# uC.net
KiCad netlist of a schematic drawn in Altium Designer
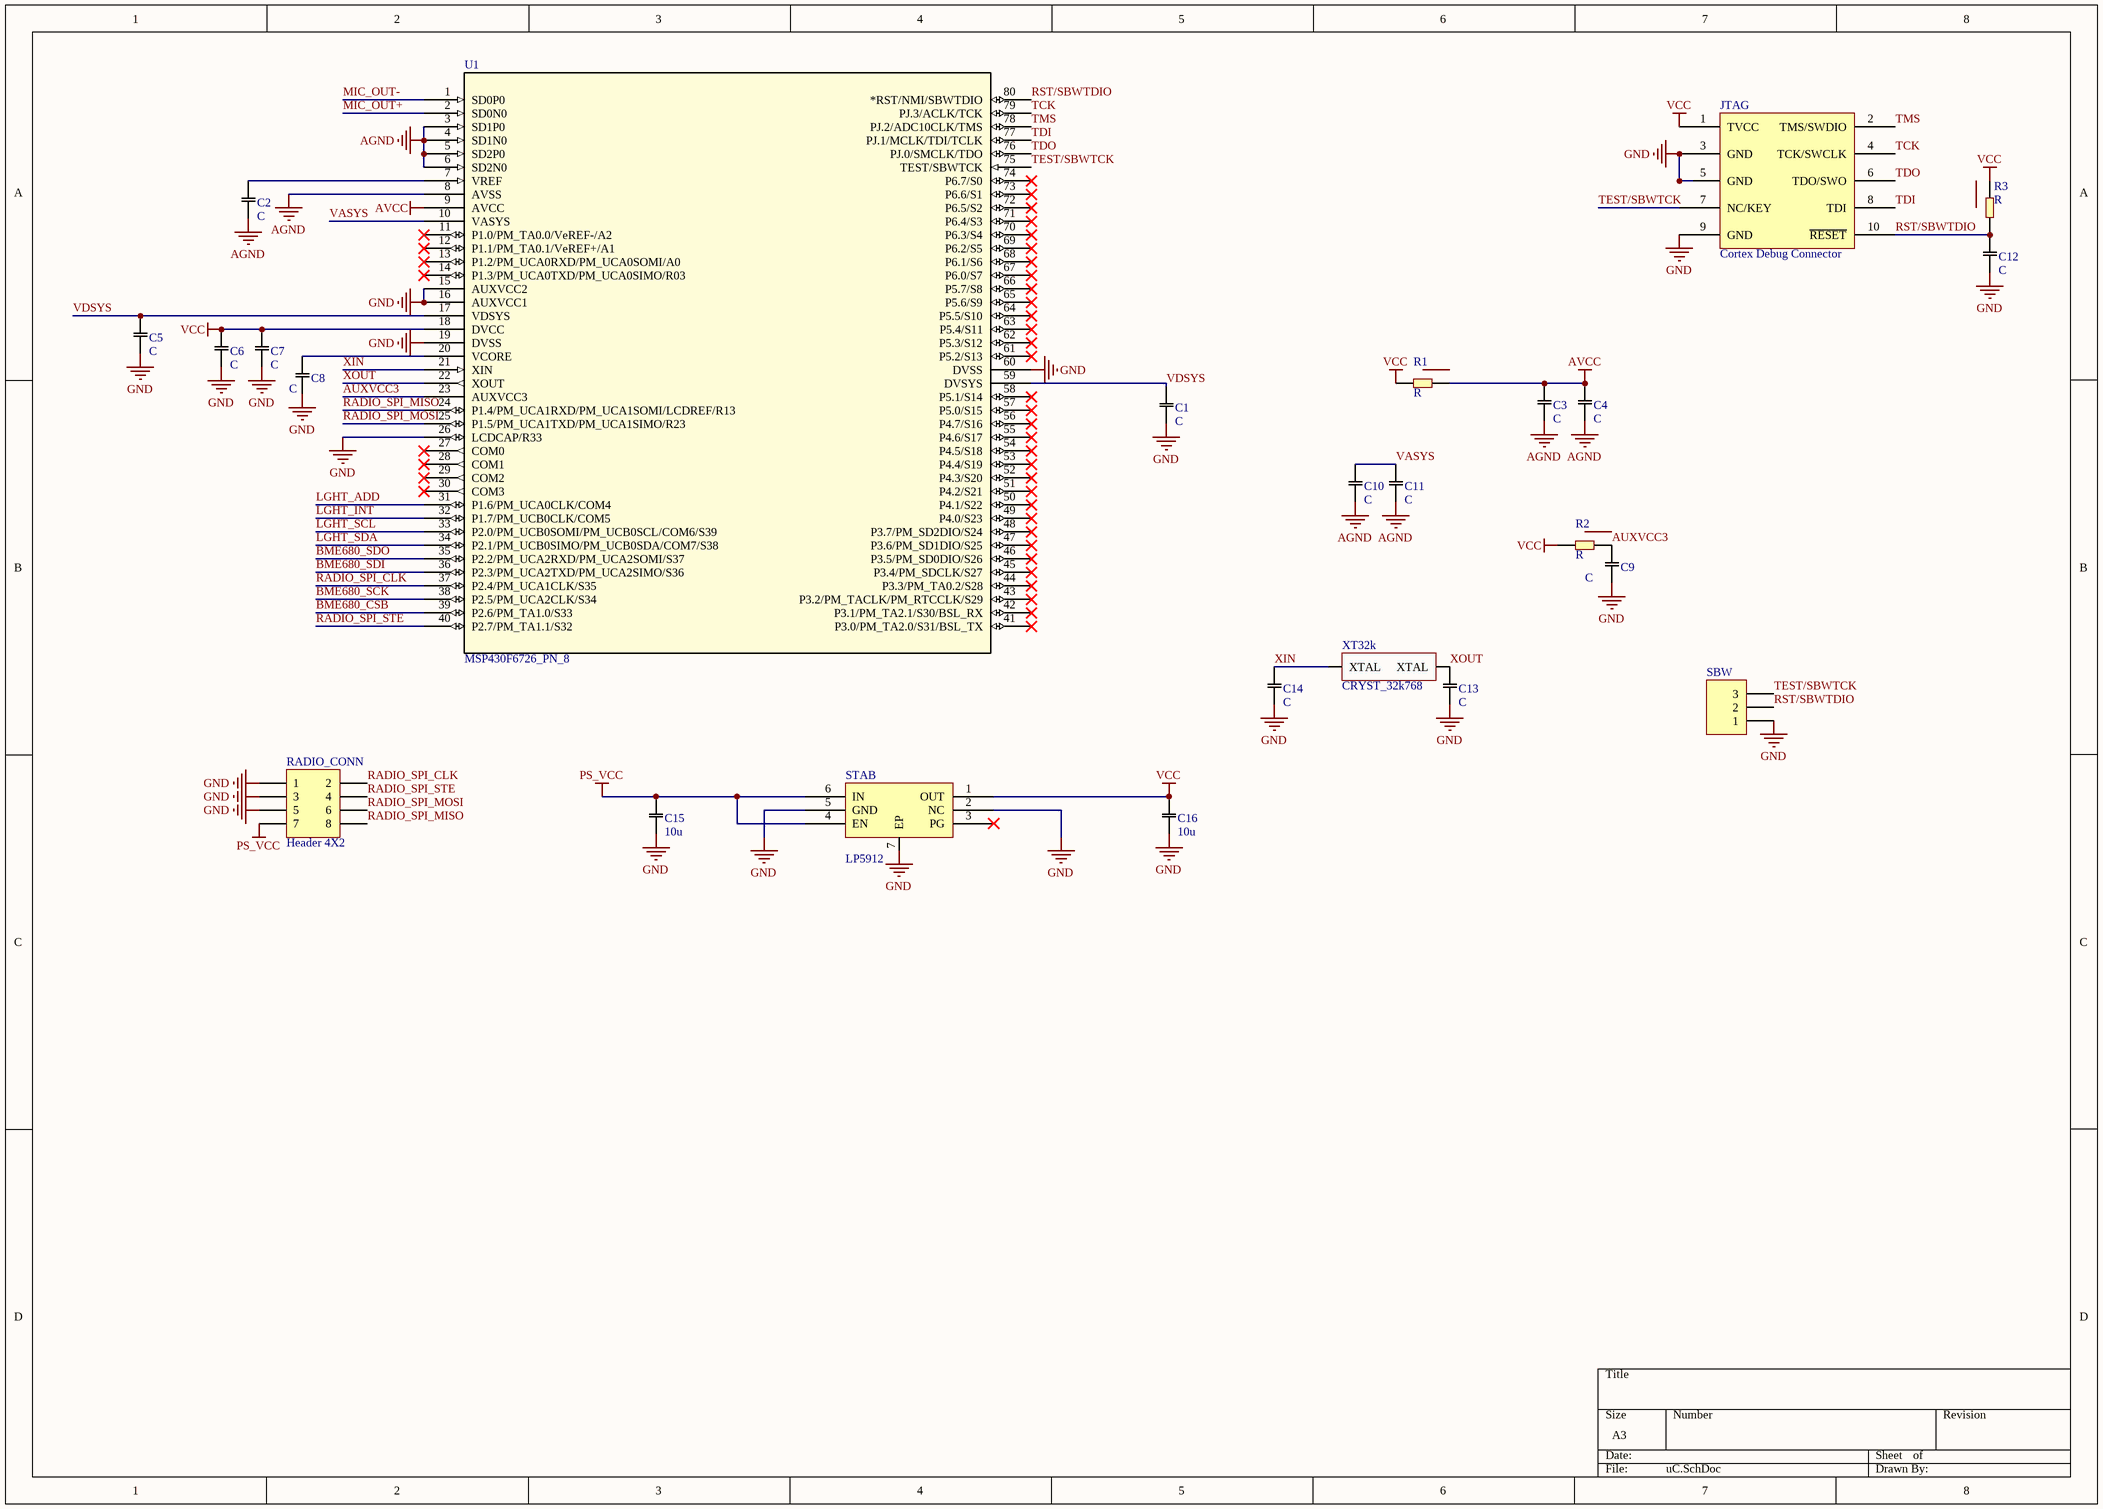
[diagram p0: uC.SchDoc]

(export (version "E")
  (design (tool "Eeschema 10.0.6"))
  (components
    (comp (ref "C1")
      (value "C")
      (footprint "402")
      (description "Capacitor")
      (libsource (lib "pass_comp") (part "C"))
    )
    (comp (ref "C2")
      (value "C")
      (footprint "402")
      (description "Capacitor")
      (libsource (lib "pass_comp") (part "C"))
    )
    (comp (ref "C3")
      (value "C")
      (footprint "402")
      (description "Capacitor")
      (libsource (lib "pass_comp") (part "C"))
    )
    (comp (ref "C4")
      (value "C")
      (footprint "402")
      (description "Capacitor")
      (libsource (lib "pass_comp") (part "C"))
    )
    (comp (ref "C5")
      (value "C")
      (footprint "402")
      (description "Capacitor")
      (libsource (lib "pass_comp") (part "C"))
    )
    (comp (ref "C6")
      (value "C")
      (footprint "402")
      (description "Capacitor")
      (libsource (lib "pass_comp") (part "C"))
    )
    (comp (ref "C7")
      (value "C")
      (footprint "402")
      (description "Capacitor")
      (libsource (lib "pass_comp") (part "C"))
    )
    (comp (ref "C8")
      (value "C")
      (footprint "402")
      (description "Capacitor")
      (libsource (lib "pass_comp") (part "C"))
    )
    (comp (ref "C9")
      (value "C")
      (footprint "402")
      (description "Capacitor")
      (libsource (lib "pass_comp") (part "C"))
    )
    (comp (ref "C10")
      (value "C")
      (footprint "402")
      (description "Capacitor")
      (libsource (lib "pass_comp") (part "C"))
    )
    (comp (ref "C11")
      (value "C")
      (footprint "402")
      (description "Capacitor")
      (libsource (lib "pass_comp") (part "C"))
    )
    (comp (ref "C12")
      (value "C")
      (footprint "402")
      (description "Capacitor")
      (libsource (lib "pass_comp") (part "C"))
    )
    (comp (ref "C13")
      (value "C")
      (footprint "402")
      (description "Capacitor")
      (libsource (lib "pass_comp") (part "C"))
    )
    (comp (ref "C14")
      (value "C")
      (footprint "402")
      (description "Capacitor")
      (libsource (lib "pass_comp") (part "C"))
    )
    (comp (ref "C15")
      (value "10u")
      (footprint "402")
      (description "Capacitor")
      (libsource (lib "pass_comp") (part "C"))
    )
    (comp (ref "C16")
      (value "10u")
      (footprint "402")
      (description "Capacitor")
      (libsource (lib "pass_comp") (part "C"))
    )
    (comp (ref "JTAG")
      (value "Cortex Debug Connector")
      (footprint "JTAG_HEADER")
      (libsource (lib "env_sens") (part "Cortex Debug Connector"))
    )
    (comp (ref "R1") (value "R") (footprint "402") (description "Resistor") (libsource (lib "") (part "R_1")))
    (comp (ref "R2") (value "R") (footprint "402") (description "Resistor") (libsource (lib "") (part "R_1")))
    (comp (ref "R3")
      (value "R")
      (footprint "402")
      (description "Resistor")
      (libsource (lib "pass_comp") (part "R"))
    )
    (comp (ref "RADIO_CONN")
      (value "Header 4X2")
      (footprint "HDR2X4")
      (description "Header, 4-Pin, Dual row")
      (fields (field (name "PUBLISHER") "Altium Limited"))
      (libsource (lib "Miscellaneous Connectors") (part "Header 4X2"))
    )
    (comp (ref "SBW")
      (value "~")
      (footprint "HDR1X3")
      (description "Header, 3-Pin")
      (fields (field (name "PUBLISHER") "Altium Limited"))
      (libsource (lib "Miscellaneous Connectors") (part "Header 3"))
    )
    (comp (ref "STAB") (value "LP5912") (footprint "WSON-6") (libsource (lib "env_sens") (part "LP5912")))
    (comp (ref "U1")
      (value "MSP430F6726_PN_8")
      (footprint "PN80-L")
      (description "Imported")
      (fields
        (field (name "MANUFACTURER_PART_NUMBER") "msp430f6726_pn_80")
        (field (name "GENERIC_PART_NUMBER") "MSP430F6726")
      )
      (libsource (lib "env_sens") (part "MSP430F6726_PN_8"))
    )
    (comp (ref "XT32k")
      (value "CRYST_32k768")
      (footprint "CRYST 32.768 kHz")
      (libsource (lib "env_sens") (part "CRYST_32k768"))
    )
  )
  (nets
    (net (code "1") (name "/AUXVCC3") (class "Default")
      (node (ref "C9") (pin "2") (pintype "passive"))
      (node (ref "R2") (pin "2") (pintype "passive"))
      (node (ref "U1") (pin "23") (pinfunction "AUXVCC3_23") (pintype "power_in"))
    )
    (net (code "2") (name "/BME680_CSB") (class "Default")
      (node (ref "U1") (pin "39") (pinfunction "P2.6/PM_TA1.0/S33_39") (pintype "bidirectional"))
    )
    (net (code "3") (name "/BME680_SCK") (class "Default")
      (node (ref "U1") (pin "38") (pinfunction "P2.5/PM_UCA2CLK/S34_38") (pintype "bidirectional"))
    )
    (net (code "4") (name "/BME680_SDI") (class "Default")
      (node (ref "U1") (pin "36") (pinfunction "P2.3/PM_UCA2TXD/PM_UCA2SIMO/S36_36") (pintype "bidirectional"))
    )
    (net (code "5") (name "/BME680_SDO") (class "Default")
      (node (ref "U1") (pin "35") (pinfunction "P2.2/PM_UCA2RXD/PM_UCA2SOMI/S37_35") (pintype "bidirectional"))
    )
    (net (code "6") (name "/LGHT_ADD") (class "Default")
      (node (ref "U1") (pin "31") (pinfunction "P1.6/PM_UCA0CLK/COM4_31") (pintype "bidirectional"))
    )
    (net (code "7") (name "/LGHT_INT") (class "Default")
      (node (ref "U1") (pin "32") (pinfunction "P1.7/PM_UCB0CLK/COM5_32") (pintype "bidirectional"))
    )
    (net (code "8") (name "/LGHT_SCL") (class "Default")
      (node (ref "U1") (pin "33") (pinfunction "P2.0/PM_UCB0SOMI/PM_UCB0SCL/COM6/S39_33") (pintype "bidirectional"))
    )
    (net (code "9") (name "/LGHT_SDA") (class "Default")
      (node (ref "U1") (pin "34") (pinfunction "P2.1/PM_UCB0SIMO/PM_UCB0SDA/COM7/S38_34") (pintype "bidirectional"))
    )
    (net (code "10") (name "/MIC_OUT+") (class "Default")
      (node (ref "U1") (pin "2") (pinfunction "SD0N0_2") (pintype "input"))
    )
    (net (code "11") (name "/MIC_OUT-") (class "Default")
      (node (ref "U1") (pin "1") (pinfunction "SD0P0_1") (pintype "input"))
    )
    (net (code "12") (name "/RADIO_SPI_CLK") (class "Default")
      (node (ref "RADIO_CONN") (pin "2") (pinfunction "2_2") (pintype "passive"))
      (node (ref "U1") (pin "37") (pinfunction "P2.4/PM_UCA1CLK/S35_37") (pintype "bidirectional"))
    )
    (net (code "13") (name "/RADIO_SPI_MISO") (class "Default")
      (node (ref "RADIO_CONN") (pin "8") (pinfunction "8_8") (pintype "passive"))
      (node (ref "U1") (pin "24") (pinfunction "P1.4/PM_UCA1RXD/PM_UCA1SOMI/LCDREF/R13_24") (pintype "bidirectional"))
    )
    (net (code "14") (name "/RADIO_SPI_MOSI") (class "Default")
      (node (ref "RADIO_CONN") (pin "6") (pinfunction "6_6") (pintype "passive"))
      (node (ref "U1") (pin "25") (pinfunction "P1.5/PM_UCA1TXD/PM_UCA1SIMO/R23_25") (pintype "bidirectional"))
    )
    (net (code "15") (name "/RADIO_SPI_STE") (class "Default")
      (node (ref "RADIO_CONN") (pin "4") (pinfunction "4_4") (pintype "passive"))
      (node (ref "U1") (pin "40") (pinfunction "P2.7/PM_TA1.1/S32_40") (pintype "bidirectional"))
    )
    (net (code "16") (name "/RST{slash}SBWTDIO") (class "Default")
      (node (ref "C12") (pin "2") (pintype "passive"))
      (node (ref "JTAG") (pin "10") (pinfunction "~{RESET}_10") (pintype "passive"))
      (node (ref "R3") (pin "1") (pintype "passive"))
      (node (ref "SBW") (pin "2") (pinfunction "2_2") (pintype "passive"))
      (node (ref "U1") (pin "80") (pinfunction "*RST/NMI/SBWTDIO_80") (pintype "bidirectional"))
    )
    (net (code "17") (name "/TCK") (class "Default")
      (node (ref "JTAG") (pin "4") (pinfunction "TCK/SWCLK_4") (pintype "passive"))
      (node (ref "U1") (pin "79") (pinfunction "PJ.3/ACLK/TCK_79") (pintype "bidirectional"))
    )
    (net (code "18") (name "/TDI") (class "Default")
      (node (ref "JTAG") (pin "8") (pinfunction "TDI_8") (pintype "passive"))
      (node (ref "U1") (pin "77") (pinfunction "PJ.1/MCLK/TDI/TCLK_77") (pintype "bidirectional"))
    )
    (net (code "19") (name "/TDO") (class "Default")
      (node (ref "JTAG") (pin "6") (pinfunction "TDO/SWO_6") (pintype "passive"))
      (node (ref "U1") (pin "76") (pinfunction "PJ.0/SMCLK/TDO_76") (pintype "bidirectional"))
    )
    (net (code "20") (name "/TEST{slash}SBWTCK") (class "Default")
      (node (ref "JTAG") (pin "7") (pinfunction "NC/KEY_7") (pintype "passive"))
      (node (ref "SBW") (pin "3") (pinfunction "3_3") (pintype "passive"))
      (node (ref "U1") (pin "75") (pinfunction "TEST/SBWTCK_75") (pintype "input"))
    )
    (net (code "21") (name "/TMS") (class "Default")
      (node (ref "JTAG") (pin "2") (pinfunction "TMS/SWDIO_2") (pintype "passive"))
      (node (ref "U1") (pin "78") (pinfunction "PJ.2/ADC10CLK/TMS_78") (pintype "bidirectional"))
    )
    (net (code "22") (name "/VASYS") (class "Default")
      (node (ref "C10") (pin "2") (pintype "passive"))
      (node (ref "C11") (pin "2") (pintype "passive"))
      (node (ref "U1") (pin "10") (pinfunction "VASYS_10") (pintype "power_in"))
    )
    (net (code "23") (name "/VDSYS") (class "Default")
      (node (ref "C1") (pin "2") (pintype "passive"))
      (node (ref "C5") (pin "2") (pintype "passive"))
      (node (ref "U1") (pin "17") (pinfunction "VDSYS_17") (pintype "power_in"))
      (node (ref "U1") (pin "59") (pinfunction "DVSYS_59") (pintype "power_in"))
    )
    (net (code "24") (name "/XIN") (class "Default")
      (node (ref "C14") (pin "2") (pintype "passive"))
      (node (ref "U1") (pin "21") (pinfunction "XIN_21") (pintype "input"))
      (node (ref "XT32k") (pin "2") (pinfunction "XTAL_2") (pintype "passive"))
    )
    (net (code "25") (name "/XOUT") (class "Default")
      (node (ref "C13") (pin "2") (pintype "passive"))
      (node (ref "U1") (pin "22") (pinfunction "XOUT_22") (pintype "output"))
      (node (ref "XT32k") (pin "1") (pinfunction "XTAL_1") (pintype "passive"))
    )
    (net (code "26") (name "AGND") (class "Default")
      (node (ref "C10") (pin "1") (pintype "passive"))
      (node (ref "C11") (pin "1") (pintype "passive"))
      (node (ref "C2") (pin "1") (pintype "passive"))
      (node (ref "C3") (pin "1") (pintype "passive"))
      (node (ref "C4") (pin "1") (pintype "passive"))
      (node (ref "U1") (pin "3") (pinfunction "SD1P0_3") (pintype "input"))
      (node (ref "U1") (pin "4") (pinfunction "SD1N0_4") (pintype "input"))
      (node (ref "U1") (pin "5") (pinfunction "SD2P0_5") (pintype "input"))
      (node (ref "U1") (pin "6") (pinfunction "SD2N0_6") (pintype "input"))
      (node (ref "U1") (pin "8") (pinfunction "AVSS_8") (pintype "power_in"))
    )
    (net (code "27") (name "AVCC") (class "Default")
      (node (ref "C3") (pin "2") (pintype "passive"))
      (node (ref "C4") (pin "2") (pintype "passive"))
      (node (ref "R1") (pin "2") (pintype "passive"))
      (node (ref "U1") (pin "9") (pinfunction "AVCC_9") (pintype "power_in"))
    )
    (net (code "28") (name "GND") (class "Default")
      (node (ref "C1") (pin "1") (pintype "passive"))
      (node (ref "C12") (pin "1") (pintype "passive"))
      (node (ref "C13") (pin "1") (pintype "passive"))
      (node (ref "C14") (pin "1") (pintype "passive"))
      (node (ref "C15") (pin "1") (pintype "passive"))
      (node (ref "C16") (pin "1") (pintype "passive"))
      (node (ref "C5") (pin "1") (pintype "passive"))
      (node (ref "C6") (pin "1") (pintype "passive"))
      (node (ref "C7") (pin "1") (pintype "passive"))
      (node (ref "C8") (pin "1") (pintype "passive"))
      (node (ref "C9") (pin "1") (pintype "passive"))
      (node (ref "JTAG") (pin "3") (pinfunction "GND_3") (pintype "passive"))
      (node (ref "JTAG") (pin "5") (pinfunction "GND_5") (pintype "passive"))
      (node (ref "JTAG") (pin "9") (pinfunction "GND_9") (pintype "passive"))
      (node (ref "RADIO_CONN") (pin "1") (pinfunction "1_1") (pintype "passive"))
      (node (ref "RADIO_CONN") (pin "3") (pinfunction "3_3") (pintype "passive"))
      (node (ref "RADIO_CONN") (pin "5") (pinfunction "5_5") (pintype "passive"))
      (node (ref "SBW") (pin "1") (pinfunction "1_1") (pintype "passive"))
      (node (ref "STAB") (pin "2") (pinfunction "NC_2") (pintype "passive"))
      (node (ref "STAB") (pin "5") (pinfunction "GND_5") (pintype "passive"))
      (node (ref "STAB") (pin "7") (pinfunction "EP_7") (pintype "passive"))
      (node (ref "U1") (pin "15") (pinfunction "AUXVCC2_15") (pintype "power_in"))
      (node (ref "U1") (pin "16") (pinfunction "AUXVCC1_16") (pintype "power_in"))
      (node (ref "U1") (pin "19") (pinfunction "DVSS_19") (pintype "power_in"))
      (node (ref "U1") (pin "26") (pinfunction "LCDCAP/R33_26") (pintype "bidirectional"))
      (node (ref "U1") (pin "60") (pinfunction "DVSS_60") (pintype "power_in"))
    )
    (net (code "29") (name "Net-(U1-VCORE)") (class "Default")
      (node (ref "C8") (pin "2") (pintype "passive"))
      (node (ref "U1") (pin "20") (pinfunction "VCORE_20") (pintype "power_in"))
    )
    (net (code "30") (name "Net-(U1-VREF)") (class "Default")
      (node (ref "C2") (pin "2") (pintype "passive"))
      (node (ref "U1") (pin "7") (pinfunction "VREF_7") (pintype "input"))
    )
    (net (code "31") (name "PS_VCC") (class "Default")
      (node (ref "C15") (pin "2") (pintype "passive"))
      (node (ref "RADIO_CONN") (pin "7") (pinfunction "7_7") (pintype "passive"))
      (node (ref "STAB") (pin "4") (pinfunction "EN_4") (pintype "passive"))
      (node (ref "STAB") (pin "6") (pinfunction "IN_6") (pintype "passive"))
    )
    (net (code "32") (name "VCC") (class "Default")
      (node (ref "C16") (pin "2") (pintype "passive"))
      (node (ref "C6") (pin "2") (pintype "passive"))
      (node (ref "C7") (pin "2") (pintype "passive"))
      (node (ref "JTAG") (pin "1") (pinfunction "TVCC_1") (pintype "passive"))
      (node (ref "R1") (pin "1") (pintype "passive"))
      (node (ref "R2") (pin "1") (pintype "passive"))
      (node (ref "R3") (pin "2") (pintype "passive"))
      (node (ref "STAB") (pin "1") (pinfunction "OUT_1") (pintype "passive"))
      (node (ref "U1") (pin "18") (pinfunction "DVCC_18") (pintype "power_in"))
    )
    (net (code "33") (name "unconnected-(STAB-PG-Pad3)") (class "Default")
      (node (ref "STAB") (pin "3") (pinfunction "PG_3") (pintype "passive+no_connect"))
    )
    (net (code "34") (name "unconnected-(U1-COM0-Pad27)") (class "Default")
      (node (ref "U1") (pin "27") (pinfunction "COM0_27") (pintype "output+no_connect"))
    )
    (net (code "35") (name "unconnected-(U1-COM1-Pad28)") (class "Default")
      (node (ref "U1") (pin "28") (pinfunction "COM1_28") (pintype "output+no_connect"))
    )
    (net (code "36") (name "unconnected-(U1-COM2-Pad29)") (class "Default")
      (node (ref "U1") (pin "29") (pinfunction "COM2_29") (pintype "output+no_connect"))
    )
    (net (code "37") (name "unconnected-(U1-COM3-Pad30)") (class "Default")
      (node (ref "U1") (pin "30") (pinfunction "COM3_30") (pintype "output+no_connect"))
    )
    (net (code "38") (name "unconnected-(U1-P1.0{slash}PM_TA0.0{slash}VeREF-{slash}A2-Pad11)") (class "Default")
      (node (ref "U1") (pin "11") (pinfunction "P1.0/PM_TA0.0/VeREF-/A2_11") (pintype "bidirectional+no_connect"))
    )
    (net (code "39") (name "unconnected-(U1-P1.1{slash}PM_TA0.1{slash}VeREF+{slash}A1-Pad12)") (class "Default")
      (node (ref "U1") (pin "12") (pinfunction "P1.1/PM_TA0.1/VeREF+/A1_12") (pintype "bidirectional+no_connect"))
    )
    (net (code "40") (name "unconnected-(U1-P1.2{slash}PM_UCA0RXD{slash}PM_UCA0SOMI{slash}A0-Pad13)") (class "Default")
      (node (ref "U1") (pin "13") (pinfunction "P1.2/PM_UCA0RXD/PM_UCA0SOMI/A0_13") (pintype "bidirectional+no_connect"))
    )
    (net (code "41") (name "unconnected-(U1-P1.3{slash}PM_UCA0TXD{slash}PM_UCA0SIMO{slash}R03-Pad14)") (class "Default")
      (node (ref "U1") (pin "14") (pinfunction "P1.3/PM_UCA0TXD/PM_UCA0SIMO/R03_14") (pintype "bidirectional+no_connect"))
    )
    (net (code "42") (name "unconnected-(U1-P3.0{slash}PM_TA2.0{slash}S31{slash}BSL_TX-Pad41)") (class "Default")
      (node (ref "U1") (pin "41") (pinfunction "P3.0/PM_TA2.0/S31/BSL_TX_41") (pintype "bidirectional+no_connect"))
    )
    (net (code "43") (name "unconnected-(U1-P3.1{slash}PM_TA2.1{slash}S30{slash}BSL_RX-Pad42)") (class "Default")
      (node (ref "U1") (pin "42") (pinfunction "P3.1/PM_TA2.1/S30/BSL_RX_42") (pintype "bidirectional+no_connect"))
    )
    (net (code "44") (name "unconnected-(U1-P3.2{slash}PM_TACLK{slash}PM_RTCCLK{slash}S29-Pad43)") (class "Default")
      (node (ref "U1") (pin "43") (pinfunction "P3.2/PM_TACLK/PM_RTCCLK/S29_43") (pintype "bidirectional+no_connect"))
    )
    (net (code "45") (name "unconnected-(U1-P3.3{slash}PM_TA0.2{slash}S28-Pad44)") (class "Default")
      (node (ref "U1") (pin "44") (pinfunction "P3.3/PM_TA0.2/S28_44") (pintype "bidirectional+no_connect"))
    )
    (net (code "46") (name "unconnected-(U1-P3.4{slash}PM_SDCLK{slash}S27-Pad45)") (class "Default")
      (node (ref "U1") (pin "45") (pinfunction "P3.4/PM_SDCLK/S27_45") (pintype "bidirectional+no_connect"))
    )
    (net (code "47") (name "unconnected-(U1-P3.5{slash}PM_SD0DIO{slash}S26-Pad46)") (class "Default")
      (node (ref "U1") (pin "46") (pinfunction "P3.5/PM_SD0DIO/S26_46") (pintype "bidirectional+no_connect"))
    )
    (net (code "48") (name "unconnected-(U1-P3.6{slash}PM_SD1DIO{slash}S25-Pad47)") (class "Default")
      (node (ref "U1") (pin "47") (pinfunction "P3.6/PM_SD1DIO/S25_47") (pintype "bidirectional+no_connect"))
    )
    (net (code "49") (name "unconnected-(U1-P3.7{slash}PM_SD2DIO{slash}S24-Pad48)") (class "Default")
      (node (ref "U1") (pin "48") (pinfunction "P3.7/PM_SD2DIO/S24_48") (pintype "bidirectional+no_connect"))
    )
    (net (code "50") (name "unconnected-(U1-P4.0{slash}S23-Pad49)") (class "Default")
      (node (ref "U1") (pin "49") (pinfunction "P4.0/S23_49") (pintype "bidirectional+no_connect"))
    )
    (net (code "51") (name "unconnected-(U1-P4.1{slash}S22-Pad50)") (class "Default")
      (node (ref "U1") (pin "50") (pinfunction "P4.1/S22_50") (pintype "bidirectional+no_connect"))
    )
    (net (code "52") (name "unconnected-(U1-P4.2{slash}S21-Pad51)") (class "Default")
      (node (ref "U1") (pin "51") (pinfunction "P4.2/S21_51") (pintype "bidirectional+no_connect"))
    )
    (net (code "53") (name "unconnected-(U1-P4.3{slash}S20-Pad52)") (class "Default")
      (node (ref "U1") (pin "52") (pinfunction "P4.3/S20_52") (pintype "bidirectional+no_connect"))
    )
    (net (code "54") (name "unconnected-(U1-P4.4{slash}S19-Pad53)") (class "Default")
      (node (ref "U1") (pin "53") (pinfunction "P4.4/S19_53") (pintype "bidirectional+no_connect"))
    )
    (net (code "55") (name "unconnected-(U1-P4.5{slash}S18-Pad54)") (class "Default")
      (node (ref "U1") (pin "54") (pinfunction "P4.5/S18_54") (pintype "bidirectional+no_connect"))
    )
    (net (code "56") (name "unconnected-(U1-P4.6{slash}S17-Pad55)") (class "Default")
      (node (ref "U1") (pin "55") (pinfunction "P4.6/S17_55") (pintype "bidirectional+no_connect"))
    )
    (net (code "57") (name "unconnected-(U1-P4.7{slash}S16-Pad56)") (class "Default")
      (node (ref "U1") (pin "56") (pinfunction "P4.7/S16_56") (pintype "bidirectional+no_connect"))
    )
    (net (code "58") (name "unconnected-(U1-P5.0{slash}S15-Pad57)") (class "Default")
      (node (ref "U1") (pin "57") (pinfunction "P5.0/S15_57") (pintype "bidirectional+no_connect"))
    )
    (net (code "59") (name "unconnected-(U1-P5.1{slash}S14-Pad58)") (class "Default")
      (node (ref "U1") (pin "58") (pinfunction "P5.1/S14_58") (pintype "bidirectional+no_connect"))
    )
    (net (code "60") (name "unconnected-(U1-P5.2{slash}S13-Pad61)") (class "Default")
      (node (ref "U1") (pin "61") (pinfunction "P5.2/S13_61") (pintype "bidirectional+no_connect"))
    )
    (net (code "61") (name "unconnected-(U1-P5.3{slash}S12-Pad62)") (class "Default")
      (node (ref "U1") (pin "62") (pinfunction "P5.3/S12_62") (pintype "bidirectional+no_connect"))
    )
    (net (code "62") (name "unconnected-(U1-P5.4{slash}S11-Pad63)") (class "Default")
      (node (ref "U1") (pin "63") (pinfunction "P5.4/S11_63") (pintype "bidirectional+no_connect"))
    )
    (net (code "63") (name "unconnected-(U1-P5.5{slash}S10-Pad64)") (class "Default")
      (node (ref "U1") (pin "64") (pinfunction "P5.5/S10_64") (pintype "bidirectional+no_connect"))
    )
    (net (code "64") (name "unconnected-(U1-P5.6{slash}S9-Pad65)") (class "Default")
      (node (ref "U1") (pin "65") (pinfunction "P5.6/S9_65") (pintype "bidirectional+no_connect"))
    )
    (net (code "65") (name "unconnected-(U1-P5.7{slash}S8-Pad66)") (class "Default")
      (node (ref "U1") (pin "66") (pinfunction "P5.7/S8_66") (pintype "bidirectional+no_connect"))
    )
    (net (code "66") (name "unconnected-(U1-P6.0{slash}S7-Pad67)") (class "Default")
      (node (ref "U1") (pin "67") (pinfunction "P6.0/S7_67") (pintype "bidirectional+no_connect"))
    )
    (net (code "67") (name "unconnected-(U1-P6.1{slash}S6-Pad68)") (class "Default")
      (node (ref "U1") (pin "68") (pinfunction "P6.1/S6_68") (pintype "bidirectional+no_connect"))
    )
    (net (code "68") (name "unconnected-(U1-P6.2{slash}S5-Pad69)") (class "Default")
      (node (ref "U1") (pin "69") (pinfunction "P6.2/S5_69") (pintype "bidirectional+no_connect"))
    )
    (net (code "69") (name "unconnected-(U1-P6.3{slash}S4-Pad70)") (class "Default")
      (node (ref "U1") (pin "70") (pinfunction "P6.3/S4_70") (pintype "bidirectional+no_connect"))
    )
    (net (code "70") (name "unconnected-(U1-P6.4{slash}S3-Pad71)") (class "Default")
      (node (ref "U1") (pin "71") (pinfunction "P6.4/S3_71") (pintype "bidirectional+no_connect"))
    )
    (net (code "71") (name "unconnected-(U1-P6.5{slash}S2-Pad72)") (class "Default")
      (node (ref "U1") (pin "72") (pinfunction "P6.5/S2_72") (pintype "bidirectional+no_connect"))
    )
    (net (code "72") (name "unconnected-(U1-P6.6{slash}S1-Pad73)") (class "Default")
      (node (ref "U1") (pin "73") (pinfunction "P6.6/S1_73") (pintype "bidirectional+no_connect"))
    )
    (net (code "73") (name "unconnected-(U1-P6.7{slash}S0-Pad74)") (class "Default")
      (node (ref "U1") (pin "74") (pinfunction "P6.7/S0_74") (pintype "bidirectional+no_connect"))
    )
  )
)
